# xxxxxx_001_sh3_RTC.net
KiCad netlist of a schematic drawn in Altium Designer
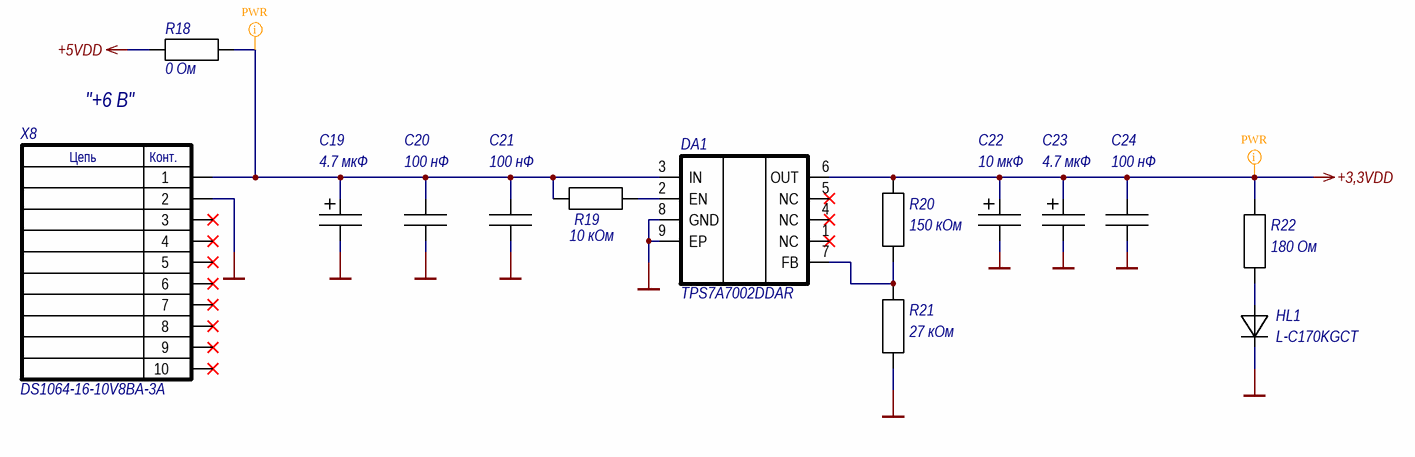
[diagram p0: xxxxxx.001_sh3_RTC.SchDoc]

(export (version "E")
  (design (tool "Eeschema 10.0.6"))
  (components
    (comp (ref "C19")
      (value "4.7 мкФ")
      (footprint "CAPMP3216X180N")
      (description "Solid Tantalum Surface Mount Capacitor")
      (fields (field (name "MANUFACTURER") "AVX") (field (name "VOLTAGE") "25 В"))
      (libsource (lib "xxxxxx001_RTC") (part "CAP_P"))
    )
    (comp (ref "C20")
      (value "100 нФ")
      (footprint "CAPC160X080X080N")
      (description "Chip Monolithic Ceramic Capacitor")
      (fields (field (name "MANUFACTURER") "Murata") (field (name "VOLTAGE") "25 В"))
      (libsource (lib "xxxxxx001_RTC") (part "CAP_NP"))
    )
    (comp (ref "C21")
      (value "100 нФ")
      (footprint "CAPC160X080X080N")
      (description "Chip Monolithic Ceramic Capacitor")
      (fields (field (name "MANUFACTURER") "Murata") (field (name "VOLTAGE") "25 В"))
      (libsource (lib "xxxxxx001_RTC") (part "CAP_NP"))
    )
    (comp (ref "C22")
      (value "10 мкФ")
      (footprint "CAPMP3216X180N")
      (description "Solid Tantalum Surface Mount Capacitor")
      (fields (field (name "MANUFACTURER") "AVX") (field (name "VOLTAGE") "16 В"))
      (libsource (lib "xxxxxx001_RTC") (part "CAP_P"))
    )
    (comp (ref "C23")
      (value "4.7 мкФ")
      (footprint "CAPMP3216X180N")
      (description "Solid Tantalum Surface Mount Capacitor")
      (fields (field (name "MANUFACTURER") "AVX") (field (name "VOLTAGE") "25 В"))
      (libsource (lib "xxxxxx001_RTC") (part "CAP_P"))
    )
    (comp (ref "C24")
      (value "100 нФ")
      (footprint "CAPC160X080X080N")
      (description "Chip Monolithic Ceramic Capacitor")
      (fields (field (name "MANUFACTURER") "Murata") (field (name "VOLTAGE") "25 В"))
      (libsource (lib "xxxxxx001_RTC") (part "CAP_NP"))
    )
    (comp (ref "DA1")
      (value "TPS7A7002DDAR")
      (footprint "SOIC127P600X170_HS-9N")
      (description "Very Low Input, Very Low Dropout 3-A Regulator With Enable")
      (fields (field (name "MANUFACTURER") "Texas Instruments"))
      (libsource (lib "xxxxxx001_RTC") (part "TPS7A7002"))
    )
    (comp (ref "HL1")
      (value "L-C170KGCT")
      (footprint "LEDC200X125X075N_RED")
      (description "Светодиод поверхностного монтажа, зеленый, 0805")
      (fields (field (name "MANUFACTURER") "Para Light"))
      (libsource (lib "xxxxxx001_RTC") (part "LED"))
    )
    (comp (ref "R18")
      (value "0 Ом")
      (footprint "RESC160X080X045N")
      (description "General Purpose Chip Resistor")
      (fields (field (name "MANUFACTURER") "Yageo") (field (name "POWER") "100 мВт"))
      (libsource (lib "xxxxxx001_RTC") (part "RES"))
    )
    (comp (ref "R19")
      (value "10 кОм")
      (footprint "RESC160X080X045N")
      (description "General Purpose Chip Resistor")
      (fields (field (name "MANUFACTURER") "Yageo") (field (name "POWER") "100 мВт"))
      (libsource (lib "xxxxxx001_RTC") (part "RES"))
    )
    (comp (ref "R20")
      (value "150 кОм")
      (footprint "RESC160X080X045N")
      (description "General Purpose Chip Resistor")
      (fields (field (name "MANUFACTURER") "Yageo") (field (name "POWER") "100 мВт"))
      (libsource (lib "") (part "RES_1"))
    )
    (comp (ref "R21")
      (value "27 кОм")
      (footprint "RESC160X080X045N")
      (description "General Purpose Chip Resistor")
      (fields (field (name "MANUFACTURER") "Yageo") (field (name "POWER") "100 мВт"))
      (libsource (lib "") (part "RES_1"))
    )
    (comp (ref "R22")
      (value "180 Ом")
      (footprint "RESC160X080X045N")
      (description "General Purpose Chip Resistor")
      (fields (field (name "MANUFACTURER") "Yageo") (field (name "POWER") "100 мВт"))
      (libsource (lib "") (part "RES_1"))
    )
    (comp (ref "X8")
      (value "DS1064-16-10V8BA-3A")
      (footprint "BHTH127x254_2X5")
      (description "1.27mm Box Header V/T Type H=7.1mm, 10 pin")
      (fields (field (name "MANUFACTURER") "Connfly"))
      (libsource (lib "xxxxxx001_RTC") (part "CONN_10P"))
    )
  )
  (nets
    (net (code "1") (name "+3,3VDD") (class "Default")
      (node (ref "C22") (pin "1") (pinfunction "1_1") (pintype "passive"))
      (node (ref "C23") (pin "1") (pinfunction "1_1") (pintype "passive"))
      (node (ref "C24") (pin "1") (pinfunction "1_1") (pintype "passive"))
      (node (ref "DA1") (pin "6") (pinfunction "OUT_6") (pintype "passive"))
      (node (ref "R20") (pin "1") (pinfunction "1_1") (pintype "passive"))
      (node (ref "R22") (pin "1") (pinfunction "1_1") (pintype "passive"))
    )
    (net (code "2") (name "+5VDD") (class "Default")
      (node (ref "R18") (pin "1") (pinfunction "1_1") (pintype "passive"))
    )
    (net (code "3") (name "GND") (class "Default")
      (node (ref "C19") (pin "2") (pinfunction "2_2") (pintype "passive"))
      (node (ref "C20") (pin "2") (pinfunction "2_2") (pintype "passive"))
      (node (ref "C21") (pin "2") (pinfunction "2_2") (pintype "passive"))
      (node (ref "C22") (pin "2") (pinfunction "2_2") (pintype "passive"))
      (node (ref "C23") (pin "2") (pinfunction "2_2") (pintype "passive"))
      (node (ref "C24") (pin "2") (pinfunction "2_2") (pintype "passive"))
      (node (ref "DA1") (pin "8") (pinfunction "GND_8") (pintype "passive"))
      (node (ref "DA1") (pin "9") (pinfunction "EP_9") (pintype "passive"))
      (node (ref "HL1") (pin "2") (pinfunction "2_2") (pintype "passive"))
      (node (ref "R21") (pin "2") (pinfunction "2_2") (pintype "passive"))
      (node (ref "X8") (pin "2") (pinfunction "2_2") (pintype "passive"))
    )
    (net (code "4") (name "Net-(DA1-EN)") (class "Default")
      (node (ref "DA1") (pin "2") (pinfunction "EN_2") (pintype "passive"))
      (node (ref "R19") (pin "2") (pinfunction "2_2") (pintype "passive"))
    )
    (net (code "5") (name "Net-(DA1-FB)") (class "Default")
      (node (ref "DA1") (pin "7") (pinfunction "FB_7") (pintype "passive"))
      (node (ref "R20") (pin "2") (pinfunction "2_2") (pintype "passive"))
      (node (ref "R21") (pin "1") (pinfunction "1_1") (pintype "passive"))
    )
    (net (code "6") (name "Net-(DA1-IN)") (class "Default")
      (node (ref "C19") (pin "1") (pinfunction "1_1") (pintype "passive"))
      (node (ref "C20") (pin "1") (pinfunction "1_1") (pintype "passive"))
      (node (ref "C21") (pin "1") (pinfunction "1_1") (pintype "passive"))
      (node (ref "DA1") (pin "3") (pinfunction "IN_3") (pintype "passive"))
      (node (ref "R18") (pin "2") (pinfunction "2_2") (pintype "passive"))
      (node (ref "R19") (pin "1") (pinfunction "1_1") (pintype "passive"))
      (node (ref "X8") (pin "1") (pinfunction "1_1") (pintype "passive"))
    )
    (net (code "7") (name "Net-(HL1-Pad1)") (class "Default")
      (node (ref "HL1") (pin "1") (pinfunction "1_1") (pintype "passive"))
      (node (ref "R22") (pin "2") (pinfunction "2_2") (pintype "passive"))
    )
    (net (code "8") (name "unconnected-(DA1-NC-Pad1)") (class "Default")
      (node (ref "DA1") (pin "1") (pinfunction "NC_1") (pintype "passive+no_connect"))
    )
    (net (code "9") (name "unconnected-(DA1-NC-Pad4)") (class "Default")
      (node (ref "DA1") (pin "4") (pinfunction "NC_4") (pintype "passive+no_connect"))
    )
    (net (code "10") (name "unconnected-(DA1-NC-Pad5)") (class "Default")
      (node (ref "DA1") (pin "5") (pinfunction "NC_5") (pintype "passive+no_connect"))
    )
    (net (code "11") (name "unconnected-(X8-Pad3)") (class "Default")
      (node (ref "X8") (pin "3") (pinfunction "3_3") (pintype "passive+no_connect"))
    )
    (net (code "12") (name "unconnected-(X8-Pad4)") (class "Default")
      (node (ref "X8") (pin "4") (pinfunction "4_4") (pintype "passive+no_connect"))
    )
    (net (code "13") (name "unconnected-(X8-Pad5)") (class "Default")
      (node (ref "X8") (pin "5") (pinfunction "5_5") (pintype "passive+no_connect"))
    )
    (net (code "14") (name "unconnected-(X8-Pad6)") (class "Default")
      (node (ref "X8") (pin "6") (pinfunction "6_6") (pintype "passive+no_connect"))
    )
    (net (code "15") (name "unconnected-(X8-Pad7)") (class "Default")
      (node (ref "X8") (pin "7") (pinfunction "7_7") (pintype "passive+no_connect"))
    )
    (net (code "16") (name "unconnected-(X8-Pad8)") (class "Default")
      (node (ref "X8") (pin "8") (pinfunction "8_8") (pintype "passive+no_connect"))
    )
    (net (code "17") (name "unconnected-(X8-Pad9)") (class "Default")
      (node (ref "X8") (pin "9") (pinfunction "9_9") (pintype "passive+no_connect"))
    )
    (net (code "18") (name "unconnected-(X8-Pad10)") (class "Default")
      (node (ref "X8") (pin "10") (pinfunction "10_10") (pintype "passive+no_connect"))
    )
  )
)
